# EVB-NORA-B2_SCHEM_0005_On-Board-Debug.net
KiCad netlist of a schematic drawn in Altium Designer
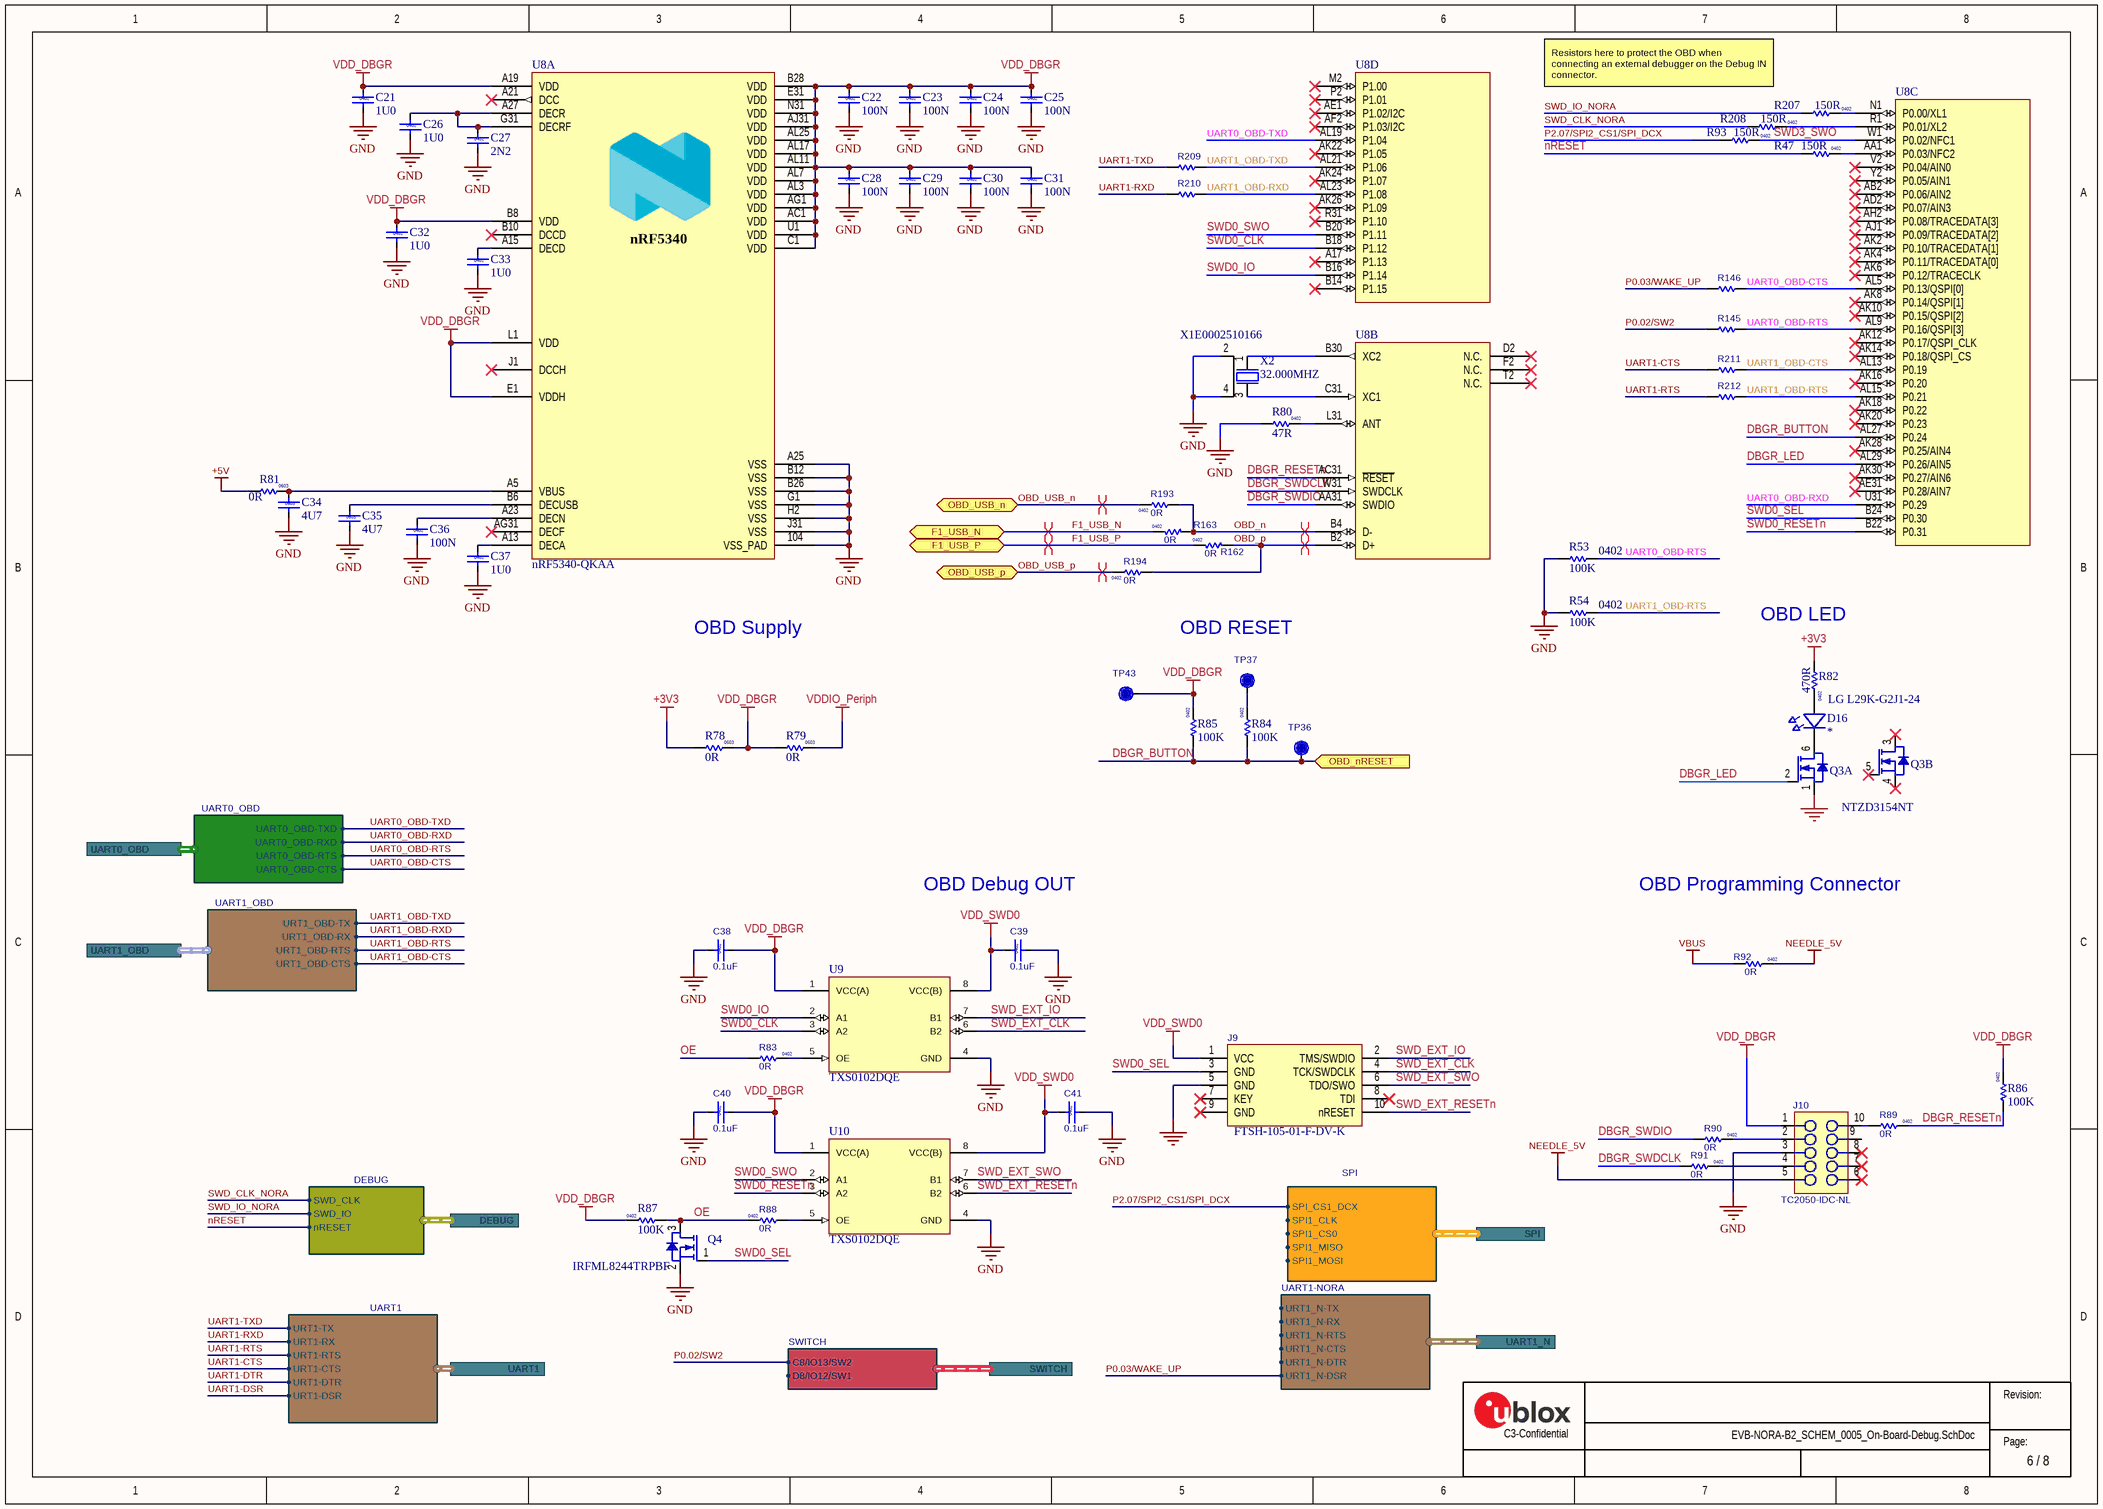
[diagram p0: EVB-NORA-B2_SCHEM_0005_On-Board-Debug.SchDoc]

(export (version "E")
  (design (tool "Eeschema 10.0.6"))
  (components
    (comp (ref "C21")
      (value "1U0")
      (footprint "Cap_0402_1100Lx600Wx600H_600x600Pad_350G_FLX")
      (description "CAP CER X5R 0402 1U0 10% 6.3V")
      (fields
        (field (name "SIZE") "0402")
        (field (name "PART NUMBER") "UBXH01-2021003")
        (field (name "TOLERANCE") "10%")
      )
      (libsource (lib "UBX_Parts_DB_Lib") (part "Cap Chip"))
    )
    (comp (ref "C22")
      (value "100N")
      (footprint "Cap 0402 HD")
      (description "CAP CER X5R 0402 100N 10% 10V")
      (fields
        (field (name "SIZE") "0402")
        (field (name "PART NUMBER") "UBXH01-2021002")
        (field (name "TOLERANCE") "10%")
      )
      (libsource (lib "UBX_Parts_DB_Lib") (part "Cap Chip"))
    )
    (comp (ref "C23")
      (value "100N")
      (footprint "Cap 0402 HD")
      (description "CAP CER X5R 0402 100N 10% 10V")
      (fields
        (field (name "SIZE") "0402")
        (field (name "PART NUMBER") "UBXH01-2021002")
        (field (name "TOLERANCE") "10%")
      )
      (libsource (lib "UBX_Parts_DB_Lib") (part "Cap Chip"))
    )
    (comp (ref "C24")
      (value "100N")
      (footprint "Cap 0402 HD")
      (description "CAP CER X5R 0402 100N 10% 10V")
      (fields
        (field (name "SIZE") "0402")
        (field (name "PART NUMBER") "UBXH01-2021002")
        (field (name "TOLERANCE") "10%")
      )
      (libsource (lib "UBX_Parts_DB_Lib") (part "Cap Chip"))
    )
    (comp (ref "C25")
      (value "100N")
      (footprint "Cap 0402 HD")
      (description "CAP CER X5R 0402 100N 10% 10V")
      (fields
        (field (name "SIZE") "0402")
        (field (name "PART NUMBER") "UBXH01-2021002")
        (field (name "TOLERANCE") "10%")
      )
      (libsource (lib "UBX_Parts_DB_Lib") (part "Cap Chip"))
    )
    (comp (ref "C26")
      (value "1U0")
      (footprint "Cap_0402_1100Lx600Wx600H_600x600Pad_350G_FLX")
      (description "CAP CER X5R 0402 1U0 10% 6.3V")
      (fields
        (field (name "SIZE") "0402")
        (field (name "PART NUMBER") "UBXH01-2021003")
        (field (name "TOLERANCE") "10%")
      )
      (libsource (lib "UBX_Parts_DB_Lib") (part "Cap Chip"))
    )
    (comp (ref "C27")
      (value "2N2")
      (footprint "Cap_0402_1100Lx600Wx600H_600x600Pad_350G_FLX")
      (description "CAP CER X7R 0402 2N2 10% 16V")
      (fields
        (field (name "SIZE") "0402")
        (field (name "PART NUMBER") "UBXH01-0023017")
        (field (name "TOLERANCE") "10%")
      )
      (libsource (lib "UBX_Parts_DB_Lib") (part "Cap Chip"))
    )
    (comp (ref "C28")
      (value "100N")
      (footprint "Cap 0402 HD")
      (description "CAP CER X5R 0402 100N 10% 10V")
      (fields
        (field (name "SIZE") "0402")
        (field (name "PART NUMBER") "UBXH01-2021002")
        (field (name "TOLERANCE") "10%")
      )
      (libsource (lib "UBX_Parts_DB_Lib") (part "Cap Chip"))
    )
    (comp (ref "C29")
      (value "100N")
      (footprint "Cap 0402 HD")
      (description "CAP CER X5R 0402 100N 10% 10V")
      (fields
        (field (name "SIZE") "0402")
        (field (name "PART NUMBER") "UBXH01-2021002")
        (field (name "TOLERANCE") "10%")
      )
      (libsource (lib "UBX_Parts_DB_Lib") (part "Cap Chip"))
    )
    (comp (ref "C30")
      (value "100N")
      (footprint "Cap 0402 HD")
      (description "CAP CER X5R 0402 100N 10% 10V")
      (fields
        (field (name "SIZE") "0402")
        (field (name "PART NUMBER") "UBXH01-2021002")
        (field (name "TOLERANCE") "10%")
      )
      (libsource (lib "UBX_Parts_DB_Lib") (part "Cap Chip"))
    )
    (comp (ref "C31")
      (value "100N")
      (footprint "Cap 0402 HD")
      (description "CAP CER X5R 0402 100N 10% 10V")
      (fields
        (field (name "SIZE") "0402")
        (field (name "PART NUMBER") "UBXH01-2021002")
        (field (name "TOLERANCE") "10%")
      )
      (libsource (lib "UBX_Parts_DB_Lib") (part "Cap Chip"))
    )
    (comp (ref "C32")
      (value "1U0")
      (footprint "Cap_0402_1100Lx600Wx600H_600x600Pad_350G_FLX")
      (description "CAP CER X5R 0402 1U0 10% 6.3V")
      (fields
        (field (name "SIZE") "0402")
        (field (name "PART NUMBER") "UBXH01-2021003")
        (field (name "TOLERANCE") "10%")
      )
      (libsource (lib "UBX_Parts_DB_Lib") (part "Cap Chip"))
    )
    (comp (ref "C33")
      (value "1U0")
      (footprint "Cap_0402_1100Lx600Wx600H_600x600Pad_350G_FLX")
      (description "CAP CER X5R 0402 1U0 10% 6.3V")
      (fields
        (field (name "SIZE") "0402")
        (field (name "PART NUMBER") "UBXH01-2021003")
        (field (name "TOLERANCE") "10%")
      )
      (libsource (lib "UBX_Parts_DB_Lib") (part "Cap Chip"))
    )
    (comp (ref "C34")
      (value "4U7")
      (footprint "CAP_0603_1750Lx950Wx850H_600x1000Pad_900G_FLX")
      (description "CAP CER X5R 0603 4U7 10% 6.3V")
      (fields
        (field (name "SIZE") "0603")
        (field (name "PART NUMBER") "UBXH01-2002003")
        (field (name "TOLERANCE") "10%")
      )
      (libsource (lib "UBX_Parts_DB_Lib") (part "Cap Chip"))
    )
    (comp (ref "C35")
      (value "4U7")
      (footprint "CAP_0603_1750Lx950Wx850H_600x1000Pad_900G_FLX")
      (description "CAP CER X5R 0603 4U7 10% 6.3V")
      (fields
        (field (name "SIZE") "0603")
        (field (name "PART NUMBER") "UBXH01-2002003")
        (field (name "TOLERANCE") "10%")
      )
      (libsource (lib "UBX_Parts_DB_Lib") (part "Cap Chip"))
    )
    (comp (ref "C36")
      (value "100N")
      (footprint "Cap 0402 HD")
      (description "CAP CER X5R 0402 100N 10% 10V")
      (fields
        (field (name "SIZE") "0402")
        (field (name "PART NUMBER") "UBXH01-2021002")
        (field (name "TOLERANCE") "10%")
      )
      (libsource (lib "UBX_Parts_DB_Lib") (part "Cap Chip"))
    )
    (comp (ref "C37")
      (value "1U0")
      (footprint "Cap_0402_1100Lx600Wx600H_600x600Pad_350G_FLX")
      (description "CAP CER X5R 0402 1U0 10% 6.3V")
      (fields
        (field (name "SIZE") "0402")
        (field (name "PART NUMBER") "UBXH01-2021003")
        (field (name "TOLERANCE") "10%")
      )
      (libsource (lib "UBX_Parts_DB_Lib") (part "Cap Chip"))
    )
    (comp (ref "C38")
      (value "0.1uF")
      (footprint "Cap 0402 HD")
      (description "Cap, Ceramic 0.1uF 10V 10% X5R 0402")
      (fields
        (field (name "SIZE") "0402")
        (field (name "PART NUMBER") "120-00016")
        (field (name "MANUFACTURER") "Murata Electronics North America")
      )
      (libsource (lib "Arena_Parts_DB_Lib") (part "Cap Chip"))
    )
    (comp (ref "C39")
      (value "0.1uF")
      (footprint "Cap 0402 HD")
      (description "Cap, Ceramic 0.1uF 10V 10% X5R 0402")
      (fields
        (field (name "SIZE") "0402")
        (field (name "PART NUMBER") "120-00016")
        (field (name "MANUFACTURER") "Murata Electronics North America")
      )
      (libsource (lib "Arena_Parts_DB_Lib") (part "Cap Chip"))
    )
    (comp (ref "C40")
      (value "0.1uF")
      (footprint "Cap 0402 HD")
      (description "Cap, Ceramic 0.1uF 10V 10% X5R 0402")
      (fields
        (field (name "SIZE") "0402")
        (field (name "PART NUMBER") "120-00016")
        (field (name "MANUFACTURER") "Murata Electronics North America")
      )
      (libsource (lib "Arena_Parts_DB_Lib") (part "Cap Chip"))
    )
    (comp (ref "C41")
      (value "0.1uF")
      (footprint "Cap 0402 HD")
      (description "Cap, Ceramic 0.1uF 10V 10% X5R 0402")
      (fields
        (field (name "SIZE") "0402")
        (field (name "PART NUMBER") "120-00016")
        (field (name "MANUFACTURER") "Murata Electronics North America")
      )
      (libsource (lib "Arena_Parts_DB_Lib") (part "Cap Chip"))
    )
    (comp (ref "D16")
      (value "UBXH11-0000018")
      (footprint "LED_0603_1600Lx800Wx400H_600x800Pad_800G_FLX")
      (description "LED CHIP 0603 LOW CURRENT OSRAM 0.002A GREEN 2.2V 2mA")
      (fields
        (field (name "COLOR") "*")
        (field (name "MANUFACTURER") "Osram")
        (field (name "MANUFACTURER P/N") "LG L29K-G2J1-24")
      )
      (libsource (lib "UBX_Parts_DB_Lib") (part "LED_BASE"))
    )
    (comp (ref "J9")
      (value "130-00099")
      (footprint "HDR.050P-10Pin-2x5-SMT_Key")
      (description "Header 0.05\" 10Pin 2Row SMD Black")
      (fields (field (name "MANUFACTURER") "Samtec") (field (name "MANUFACTURER P/N") "FTSH-105-01-F-DV-K"))
      (libsource (lib "Arena_Parts_DB_Lib") (part "JTAG-10Pin"))
    )
    (comp (ref "J10")
      (value "TC2050-IDC-NL")
      (footprint "TC2050-IDC-NL")
      (description "CON PADS FOR CBL PLUG-OF-NAILS 10-PIN NO LEGS")
      (fields (field (name "MANUFACTURER P/N") "TC2050-IDC-NL") (field (name "MANUFACTURER") "TAG Connect"))
      (libsource (lib "LEGACY_Rigado_AltiumLib") (part "CON-10Pin_2Row_ALT"))
    )
    (comp (ref "Q3")
      (value "NTZD3154NT")
      (footprint "SOT-563")
      (description "DUAL N-CHANNEL SMALL SIGNAL MOSFET SOT-563-6 PACKAGE")
      (fields (field (name "MANUFACTURER") "ON Semiconductor") (field (name "PART NUMBER") "UBXH20-0000083"))
      (libsource (lib "UBX_Parts_DB_Lib") (part "MOSFET-N-Dual"))
    )
    (comp (ref "Q4")
      (value "IRFML8244TRPBF")
      (footprint "SOT-23")
      (description "N-CHANNEL 25V HEXFET SOT23 25V 5.8A")
      (fields
        (field (name "PART NUMBER") "UBXH20-0000036")
        (field (name "MANUFACTURER") "IR International Rectifier")
      )
      (libsource (lib "UBX_Parts_DB_Lib") (part "MOSFET-N"))
    )
    (comp (ref "R47")
      (value "150R")
      (footprint "RES_0402_1100Lx600Wx400H_500x600Pad_400G_FLX")
      (description "RES THICK FILM CHIP 0402 150R 5% 63mW")
      (fields
        (field (name "SIZE") "0402")
        (field (name "PART NUMBER") "UBXH18-0008029")
        (field (name "TOLERANCE") "5%")
      )
      (libsource (lib "UBX_Parts_DB_Lib") (part "Res sm"))
    )
    (comp (ref "R53")
      (value "100K")
      (footprint "RES 0402 HD")
      (description "RES THICK FILM CHIP 0402 100K 1% 63mW")
      (fields
        (field (name "SIZE") "0402")
        (field (name "PART NUMBER") "UBXH18-0000005")
        (field (name "TOLERANCE") "1%")
      )
      (libsource (lib "UBX_Parts_DB_Lib") (part "Res sm"))
    )
    (comp (ref "R54")
      (value "100K")
      (footprint "RES 0402 HD")
      (description "RES THICK FILM CHIP 0402 100K 1% 63mW")
      (fields
        (field (name "SIZE") "0402")
        (field (name "PART NUMBER") "UBXH18-0000005")
        (field (name "TOLERANCE") "1%")
      )
      (libsource (lib "UBX_Parts_DB_Lib") (part "Res sm"))
    )
    (comp (ref "R78")
      (value "0R")
      (footprint "RES_0603_1700Lx950Wx600H_600x1000Pad_800G_FLX")
      (description "RES THICK FILM CHIP 0603 0R 0 100mW")
      (fields
        (field (name "SIZE") "0603")
        (field (name "PART NUMBER") "UBXH18-0003001")
        (field (name "TOLERANCE") "0")
      )
      (libsource (lib "UBX_Parts_DB_Lib") (part "Res sm"))
    )
    (comp (ref "R79")
      (value "0R")
      (footprint "RES_0603_1700Lx950Wx600H_600x1000Pad_800G_FLX")
      (description "RES THICK FILM CHIP 0603 0R 0 100mW")
      (fields
        (field (name "SIZE") "0603")
        (field (name "PART NUMBER") "UBXH18-0003001")
        (field (name "TOLERANCE") "0")
      )
      (libsource (lib "UBX_Parts_DB_Lib") (part "Res sm"))
    )
    (comp (ref "R80")
      (value "47R")
      (footprint "RES_0402_1100Lx600Wx400H_500x600Pad_400G_FLX")
      (description "RES THICK FILM CHIP 0402 47R 5% 100mW")
      (fields
        (field (name "SIZE") "0402")
        (field (name "PART NUMBER") "UBXH18-0008017")
        (field (name "TOLERANCE") "5%")
      )
      (libsource (lib "UBX_Parts_DB_Lib") (part "Res sm"))
    )
    (comp (ref "R81")
      (value "0R")
      (footprint "RES_0603_1700Lx950Wx600H_600x1000Pad_800G_FLX")
      (description "RES THICK FILM CHIP 0603 0R 0 100mW")
      (fields
        (field (name "SIZE") "0603")
        (field (name "PART NUMBER") "UBXH18-0003001")
        (field (name "TOLERANCE") "0")
      )
      (libsource (lib "UBX_Parts_DB_Lib") (part "Res sm"))
    )
    (comp (ref "R82")
      (value "470R")
      (footprint "RES_0402_1100Lx600Wx400H_500x600Pad_400G_FLX")
      (description "RES THICK FILM CHIP 0402 470R 5% 100mW")
      (fields
        (field (name "SIZE") "0402")
        (field (name "PART NUMBER") "UBXH18-0008041")
        (field (name "TOLERANCE") "5%")
      )
      (libsource (lib "UBX_Parts_DB_Lib") (part "Res sm"))
    )
    (comp (ref "R83")
      (value "0R")
      (footprint "RES 0402 HD")
      (description "RES THICK FILM CHIP 0402 0R 0 100mW")
      (fields
        (field (name "SIZE") "0402")
        (field (name "PART NUMBER") "UBXH18-0003002")
        (field (name "TOLERANCE") "0")
      )
      (libsource (lib "UBX_Parts_DB_Lib") (part "Res sm"))
    )
    (comp (ref "R84")
      (value "100K")
      (footprint "RES 0402 HD")
      (description "RES THICK FILM CHIP 0402 100K 1% 63mW")
      (fields
        (field (name "SIZE") "0402")
        (field (name "PART NUMBER") "UBXH18-0000005")
        (field (name "TOLERANCE") "1%")
      )
      (libsource (lib "UBX_Parts_DB_Lib") (part "Res sm"))
    )
    (comp (ref "R85")
      (value "100K")
      (footprint "RES 0402 HD")
      (description "RES THICK FILM CHIP 0402 100K 1% 63mW")
      (fields
        (field (name "SIZE") "0402")
        (field (name "PART NUMBER") "UBXH18-0000005")
        (field (name "TOLERANCE") "1%")
      )
      (libsource (lib "UBX_Parts_DB_Lib") (part "Res sm"))
    )
    (comp (ref "R86")
      (value "100K")
      (footprint "RES 0402 HD")
      (description "RES THICK FILM CHIP 0402 100K 1% 63mW")
      (fields
        (field (name "SIZE") "0402")
        (field (name "PART NUMBER") "UBXH18-0000005")
        (field (name "TOLERANCE") "1%")
      )
      (libsource (lib "UBX_Parts_DB_Lib") (part "Res sm"))
    )
    (comp (ref "R87")
      (value "100K")
      (footprint "RES 0402 HD")
      (description "RES THICK FILM CHIP 0402 100K 1% 63mW")
      (fields
        (field (name "SIZE") "0402")
        (field (name "PART NUMBER") "UBXH18-0000005")
        (field (name "TOLERANCE") "1%")
      )
      (libsource (lib "UBX_Parts_DB_Lib") (part "Res sm"))
    )
    (comp (ref "R88")
      (value "0R")
      (footprint "RES 0402 HD")
      (description "RES THICK FILM CHIP 0402 0R 0 100mW")
      (fields
        (field (name "SIZE") "0402")
        (field (name "PART NUMBER") "UBXH18-0003002")
        (field (name "TOLERANCE") "0")
      )
      (libsource (lib "UBX_Parts_DB_Lib") (part "Res sm"))
    )
    (comp (ref "R89")
      (value "0R")
      (footprint "RES 0402 HD")
      (description "RES THICK FILM CHIP 0402 0R 0 100mW")
      (fields
        (field (name "SIZE") "0402")
        (field (name "PART NUMBER") "UBXH18-0003002")
        (field (name "TOLERANCE") "0")
      )
      (libsource (lib "UBX_Parts_DB_Lib") (part "Res sm"))
    )
    (comp (ref "R90")
      (value "0R")
      (footprint "RES 0402 HD")
      (description "RES THICK FILM CHIP 0402 0R 0 100mW")
      (fields
        (field (name "SIZE") "0402")
        (field (name "PART NUMBER") "UBXH18-0003002")
        (field (name "TOLERANCE") "0")
      )
      (libsource (lib "UBX_Parts_DB_Lib") (part "Res sm"))
    )
    (comp (ref "R91")
      (value "0R")
      (footprint "RES 0402 HD")
      (description "RES THICK FILM CHIP 0402 0R 0 100mW")
      (fields
        (field (name "SIZE") "0402")
        (field (name "PART NUMBER") "UBXH18-0003002")
        (field (name "TOLERANCE") "0")
      )
      (libsource (lib "UBX_Parts_DB_Lib") (part "Res sm"))
    )
    (comp (ref "R92")
      (value "0R")
      (footprint "RES 0402 HD")
      (description "RES THICK FILM CHIP 0402 0R 0 100mW")
      (fields
        (field (name "SIZE") "0402")
        (field (name "PART NUMBER") "UBXH18-0003002")
        (field (name "TOLERANCE") "0")
      )
      (libsource (lib "UBX_Parts_DB_Lib") (part "Res sm"))
    )
    (comp (ref "R93")
      (value "150R")
      (footprint "RES_0402_1100Lx600Wx400H_500x600Pad_400G_FLX")
      (description "RES THICK FILM CHIP 0402 150R 5% 63mW")
      (fields
        (field (name "SIZE") "0402")
        (field (name "PART NUMBER") "UBXH18-0008029")
        (field (name "TOLERANCE") "5%")
      )
      (libsource (lib "UBX_Parts_DB_Lib") (part "Res sm"))
    )
    (comp (ref "R145")
      (value "UBXH18-0003002")
      (footprint "RES 0402 HD")
      (description "RES THICK FILM CHIP 0402 0R 0 100mW")
      (fields (field (name "TOLERANCE") "0") (field (name "MANUFACTURER") "KOA"))
      (libsource (lib "UBX_Parts_DB_Lib") (part "Res sm"))
    )
    (comp (ref "R146")
      (value "UBXH18-0003002")
      (footprint "RES 0402 HD")
      (description "RES THICK FILM CHIP 0402 0R 0 100mW")
      (fields (field (name "TOLERANCE") "0") (field (name "MANUFACTURER") "KOA"))
      (libsource (lib "UBX_Parts_DB_Lib") (part "Res sm"))
    )
    (comp (ref "R162")
      (value "0R")
      (footprint "RES 0402 HD")
      (description "RES THICK FILM CHIP 0402 0R 0 100mW")
      (fields
        (field (name "SIZE") "0402")
        (field (name "PART NUMBER") "UBXH18-0003002")
        (field (name "TOLERANCE") "0")
      )
      (libsource (lib "UBX_Parts_DB_Lib") (part "Res sm"))
    )
    (comp (ref "R163")
      (value "0R")
      (footprint "RES 0402 HD")
      (description "RES THICK FILM CHIP 0402 0R 0 100mW")
      (fields
        (field (name "SIZE") "0402")
        (field (name "PART NUMBER") "UBXH18-0003002")
        (field (name "TOLERANCE") "0")
      )
      (libsource (lib "UBX_Parts_DB_Lib") (part "Res sm"))
    )
    (comp (ref "R193")
      (value "0R")
      (footprint "RES 0402 HD")
      (description "RES THICK FILM CHIP 0402 0R 0 100mW")
      (fields
        (field (name "SIZE") "0402")
        (field (name "PART NUMBER") "UBXH18-0003002")
        (field (name "TOLERANCE") "0")
      )
      (libsource (lib "UBX_Parts_DB_Lib") (part "Res sm"))
    )
    (comp (ref "R194")
      (value "0R")
      (footprint "RES 0402 HD")
      (description "RES THICK FILM CHIP 0402 0R 0 100mW")
      (fields
        (field (name "SIZE") "0402")
        (field (name "PART NUMBER") "UBXH18-0003002")
        (field (name "TOLERANCE") "0")
      )
      (libsource (lib "UBX_Parts_DB_Lib") (part "Res sm"))
    )
    (comp (ref "R207")
      (value "150R")
      (footprint "RES_0402_1100Lx600Wx400H_500x600Pad_400G_FLX")
      (description "RES THICK FILM CHIP 0402 150R 5% 63mW")
      (fields
        (field (name "SIZE") "0402")
        (field (name "PART NUMBER") "UBXH18-0008029")
        (field (name "TOLERANCE") "5%")
      )
      (libsource (lib "UBX_Parts_DB_Lib") (part "Res sm"))
    )
    (comp (ref "R208")
      (value "150R")
      (footprint "RES_0402_1100Lx600Wx400H_500x600Pad_400G_FLX")
      (description "RES THICK FILM CHIP 0402 150R 5% 63mW")
      (fields
        (field (name "SIZE") "0402")
        (field (name "PART NUMBER") "UBXH18-0008029")
        (field (name "TOLERANCE") "5%")
      )
      (libsource (lib "UBX_Parts_DB_Lib") (part "Res sm"))
    )
    (comp (ref "R209")
      (value "UBXH18-0003002")
      (footprint "RES 0402 HD")
      (description "RES THICK FILM CHIP 0402 0R 0 100mW")
      (fields (field (name "TOLERANCE") "0") (field (name "MANUFACTURER") "KOA"))
      (libsource (lib "UBX_Parts_DB_Lib") (part "Res sm"))
    )
    (comp (ref "R210")
      (value "UBXH18-0003002")
      (footprint "RES 0402 HD")
      (description "RES THICK FILM CHIP 0402 0R 0 100mW")
      (fields (field (name "TOLERANCE") "0") (field (name "MANUFACTURER") "KOA"))
      (libsource (lib "UBX_Parts_DB_Lib") (part "Res sm"))
    )
    (comp (ref "R211")
      (value "UBXH18-0003002")
      (footprint "RES 0402 HD")
      (description "RES THICK FILM CHIP 0402 0R 0 100mW")
      (fields (field (name "TOLERANCE") "0") (field (name "MANUFACTURER") "KOA"))
      (libsource (lib "UBX_Parts_DB_Lib") (part "Res sm"))
    )
    (comp (ref "R212")
      (value "UBXH18-0003002")
      (footprint "RES 0402 HD")
      (description "RES THICK FILM CHIP 0402 0R 0 100mW")
      (fields (field (name "TOLERANCE") "0") (field (name "MANUFACTURER") "KOA"))
      (libsource (lib "UBX_Parts_DB_Lib") (part "Res sm"))
    )
    (comp (ref "TP36")
      (value "TP10R")
      (footprint "TP10R")
      (description "Testpoint, Round 1.0mm Dia")
      (libsource (lib "LEGACY_Rigado_AltiumLib") (part "TP_R"))
    )
    (comp (ref "TP37")
      (value "TP10R")
      (footprint "TP10R")
      (description "Testpoint, Round 1.0mm Dia")
      (libsource (lib "LEGACY_Rigado_AltiumLib") (part "TP_R"))
    )
    (comp (ref "TP43")
      (value "TP10R")
      (footprint "TP10R")
      (description "Testpoint, Round 1.0mm Dia")
      (libsource (lib "LEGACY_Rigado_AltiumLib") (part "TP_R"))
    )
    (comp (ref "U8")
      (value "UBXH12-0000420")
      (footprint "nRF5340_AQFN94")
      (description "BT5/802.15.4 SOC NORDIC NRF5340 2.4GHZ")
      (fields
        (field (name "MANUFACTURER") "Nordic Semiconductor")
        (field (name "MANUFACTURER P/N") "nRF5340-QKAA")
      )
      (libsource (lib "UBX_Parts_DB_Lib") (part "nRF5340_qkaa"))
    )
    (comp (ref "U9")
      (value "TXS0102DQE")
      (footprint "DQE0008A")
      (description "TXS0102 2-BIT BIDIRECTIONAL VOLTAGE-LEVEL TRANSLATOR X2SON-8 TXS0102DQE 5.5V")
      (fields (field (name "PART NUMBER") "UBXH10-0000108") (field (name "MANUFACTURER") "Texas Instruments"))
      (libsource (lib "UBX_Parts_DB_Lib") (part "TXS0102DQE"))
    )
    (comp (ref "U10")
      (value "TXS0102DQE")
      (footprint "DQE0008A")
      (description "TXS0102 2-BIT BIDIRECTIONAL VOLTAGE-LEVEL TRANSLATOR X2SON-8 TXS0102DQE 5.5V")
      (fields (field (name "PART NUMBER") "UBXH10-0000108") (field (name "MANUFACTURER") "Texas Instruments"))
      (libsource (lib "UBX_Parts_DB_Lib") (part "TXS0102DQE"))
    )
    (comp (ref "X2")
      (value "32.000MHZ")
      (footprint "XTAL_1612")
      (description "CRYSTAL 32MHZ CL=8PF 1.6X1.2 MM 32.000MHZ +/-10PPM@25C+/-20PPM@-40/+85+/-1PPMAGEING")
      (fields
        (field (name "PART NUMBER") "UBXH21-0000240")
        (field (name "TOLERANCE") "+/-10PPM@25C+/-20PPM@-40/+85+/-1PPMAGEING")
        (field (name "MANUFACTURER P/N") "X1E0002510166")
      )
      (libsource (lib "UBX_Parts_DB_Lib") (part "XTAL_4Pin"))
    )
  )
  (nets
    (net (code "8") (name "+3V3") (class "Default")
      (node (ref "R78") (pin "1") (pinfunction "1_1") (pintype "passive"))
      (node (ref "R82") (pin "1") (pinfunction "1_1") (pintype "passive"))
    )
    (net (code "9") (name "+5V") (class "Default")
      (node (ref "R81") (pin "1") (pinfunction "1_1") (pintype "passive"))
    )
    (net (code "10") (name "/DBGR_BUTTON") (class "Default")
      (node (ref "R84") (pin "1") (pinfunction "1_1") (pintype "passive"))
      (node (ref "R85") (pin "1") (pinfunction "1_1") (pintype "passive"))
      (node (ref "TP36") (pin "1") (pintype "passive"))
      (node (ref "U8") (pin "AL27") (pinfunction "P0.24_AL27") (pintype "bidirectional"))
    )
    (net (code "11") (name "/DBGR_LED") (class "Default")
      (node (ref "Q3") (pin "2") (pinfunction "G1_2") (pintype "passive"))
      (node (ref "U8") (pin "AL29") (pinfunction "P0.26/AIN5_AL29") (pintype "bidirectional"))
    )
    (net (code "12") (name "/DBGR_RESETn") (class "Default")
      (node (ref "R86") (pin "1") (pinfunction "1_1") (pintype "passive"))
      (node (ref "R89") (pin "1") (pinfunction "1_1") (pintype "passive"))
      (node (ref "U8") (pin "AC31") (pinfunction "~{RESET}_AC31") (pintype "input"))
    )
    (net (code "13") (name "/DBGR_SWDCLK") (class "Default")
      (node (ref "R91") (pin "2") (pinfunction "2_2") (pintype "passive"))
      (node (ref "U8") (pin "W31") (pinfunction "SWDCLK_W31") (pintype "input"))
    )
    (net (code "14") (name "/DBGR_SWDIO") (class "Default")
      (node (ref "R90") (pin "2") (pinfunction "2_2") (pintype "passive"))
      (node (ref "U8") (pin "AA31") (pinfunction "SWDIO_AA31") (pintype "bidirectional"))
    )
    (net (code "15") (name "/F1_USB_N") (class "Default")
      (node (ref "R163") (pin "2") (pinfunction "2_2") (pintype "passive"))
    )
    (net (code "16") (name "/F1_USB_P") (class "Default")
      (node (ref "R162") (pin "2") (pinfunction "2_2") (pintype "passive"))
    )
    (net (code "17") (name "/OBD_USB_n") (class "Default")
      (node (ref "R193") (pin "2") (pinfunction "2_2") (pintype "passive"))
    )
    (net (code "18") (name "/OBD_USB_p") (class "Default")
      (node (ref "R194") (pin "2") (pinfunction "2_2") (pintype "passive"))
    )
    (net (code "19") (name "/OBD_n") (class "Default")
      (node (ref "R163") (pin "1") (pinfunction "1_1") (pintype "passive"))
      (node (ref "R193") (pin "1") (pinfunction "1_1") (pintype "passive"))
      (node (ref "U8") (pin "B4") (pinfunction "D-_B4") (pintype "bidirectional"))
    )
    (net (code "20") (name "/OBD_p") (class "Default")
      (node (ref "R162") (pin "1") (pinfunction "1_1") (pintype "passive"))
      (node (ref "R194") (pin "1") (pinfunction "1_1") (pintype "passive"))
      (node (ref "U8") (pin "B2") (pinfunction "D+_B2") (pintype "bidirectional"))
    )
    (net (code "21") (name "/OE") (class "Default")
      (node (ref "Q4") (pin "3") (pinfunction "D_3") (pintype "passive"))
      (node (ref "R83") (pin "2") (pinfunction "2_2") (pintype "passive"))
      (node (ref "R87") (pin "1") (pinfunction "1_1") (pintype "passive"))
      (node (ref "R88") (pin "1") (pinfunction "1_1") (pintype "passive"))
    )
    (net (code "22") (name "/P0.02{slash}SW2") (class "Default")
      (node (ref "R145") (pin "2") (pinfunction "2_2") (pintype "passive"))
    )
    (net (code "23") (name "/P0.03{slash}WAKE_UP") (class "Default")
      (node (ref "R146") (pin "2") (pinfunction "2_2") (pintype "passive"))
    )
    (net (code "24") (name "/P2.07{slash}SPI2_CS1{slash}SPI_DCX") (class "Default")
      (node (ref "R93") (pin "1") (pinfunction "1_1") (pintype "passive"))
    )
    (net (code "25") (name "/SWD0_CLK") (class "Default")
      (node (ref "U8") (pin "B18") (pinfunction "P1.12_B18") (pintype "bidirectional"))
      (node (ref "U9") (pin "3") (pinfunction "A2_3") (pintype "bidirectional"))
    )
    (net (code "26") (name "/SWD0_IO") (class "Default")
      (node (ref "U8") (pin "B16") (pinfunction "P1.14_B16") (pintype "bidirectional"))
      (node (ref "U9") (pin "2") (pinfunction "A1_2") (pintype "bidirectional"))
    )
    (net (code "27") (name "/SWD0_RESETn") (class "Default")
      (node (ref "U10") (pin "3") (pinfunction "A2_3") (pintype "bidirectional"))
      (node (ref "U8") (pin "B22") (pinfunction "P0.31_B22") (pintype "bidirectional"))
    )
    (net (code "28") (name "/SWD0_SEL") (class "Default")
      (node (ref "J9") (pin "3") (pinfunction "GND_3") (pintype "passive"))
      (node (ref "Q4") (pin "1") (pinfunction "G_1") (pintype "passive"))
      (node (ref "U8") (pin "B24") (pinfunction "P0.30_B24") (pintype "bidirectional"))
    )
    (net (code "29") (name "/SWD0_SWO") (class "Default")
      (node (ref "U10") (pin "2") (pinfunction "A1_2") (pintype "bidirectional"))
      (node (ref "U8") (pin "B20") (pinfunction "P1.11_B20") (pintype "bidirectional"))
    )
    (net (code "30") (name "/SWD3_SWO") (class "Default")
      (node (ref "R93") (pin "2") (pinfunction "2_2") (pintype "passive"))
      (node (ref "U8") (pin "W1") (pinfunction "P0.02/NFC1_W1") (pintype "bidirectional"))
    )
    (net (code "31") (name "/SWD_CLK_NORA") (class "Default")
      (node (ref "R208") (pin "1") (pinfunction "1_1") (pintype "passive"))
    )
    (net (code "32") (name "/SWD_EXT_CLK") (class "Default")
      (node (ref "J9") (pin "4") (pinfunction "TCK/SWDCLK_4") (pintype "passive"))
      (node (ref "U9") (pin "6") (pinfunction "B2_6") (pintype "bidirectional"))
    )
    (net (code "33") (name "/SWD_EXT_IO") (class "Default")
      (node (ref "J9") (pin "2") (pinfunction "TMS/SWDIO_2") (pintype "passive"))
      (node (ref "U9") (pin "7") (pinfunction "B1_7") (pintype "bidirectional"))
    )
    (net (code "34") (name "/SWD_EXT_RESETn") (class "Default")
      (node (ref "J9") (pin "10") (pinfunction "nRESET_10") (pintype "passive"))
      (node (ref "U10") (pin "6") (pinfunction "B2_6") (pintype "bidirectional"))
    )
    (net (code "35") (name "/SWD_EXT_SWO") (class "Default")
      (node (ref "J9") (pin "6") (pinfunction "TDO/SWO_6") (pintype "passive"))
      (node (ref "U10") (pin "7") (pinfunction "B1_7") (pintype "bidirectional"))
    )
    (net (code "36") (name "/SWD_IO_NORA") (class "Default")
      (node (ref "R207") (pin "1") (pinfunction "1_1") (pintype "passive"))
    )
    (net (code "37") (name "/UART0_OBD-CTS") (class "Default")
      (node (ref "R146") (pin "1") (pinfunction "1_1") (pintype "passive"))
      (node (ref "U8") (pin "AL5") (pinfunction "P0.13/QSPI[0]_AL5") (pintype "bidirectional"))
    )
    (net (code "38") (name "/UART0_OBD-RTS") (class "Default")
      (node (ref "R145") (pin "1") (pinfunction "1_1") (pintype "passive"))
      (node (ref "R53") (pin "2") (pinfunction "2_2") (pintype "passive"))
      (node (ref "U8") (pin "AL9") (pinfunction "P0.16/QSPI[3]_AL9") (pintype "bidirectional"))
    )
    (net (code "39") (name "/UART0_OBD-RXD") (class "Default")
      (node (ref "U8") (pin "U31") (pinfunction "P0.29_U31") (pintype "bidirectional"))
    )
    (net (code "40") (name "/UART0_OBD-TXD") (class "Default")
      (node (ref "U8") (pin "AL19") (pinfunction "P1.04_AL19") (pintype "bidirectional"))
    )
    (net (code "41") (name "/UART1-CTS") (class "Default")
      (node (ref "R211") (pin "2") (pinfunction "2_2") (pintype "passive"))
    )
    (net (code "44") (name "/UART1-RTS") (class "Default")
      (node (ref "R212") (pin "2") (pinfunction "2_2") (pintype "passive"))
    )
    (net (code "45") (name "/UART1-RXD") (class "Default")
      (node (ref "R210") (pin "2") (pinfunction "2_2") (pintype "passive"))
    )
    (net (code "46") (name "/UART1-TXD") (class "Default")
      (node (ref "R209") (pin "2") (pinfunction "2_2") (pintype "passive"))
    )
    (net (code "47") (name "/UART1_OBD-CTS") (class "Default")
      (node (ref "R211") (pin "1") (pinfunction "1_1") (pintype "passive"))
      (node (ref "U8") (pin "AL13") (pinfunction "P0.19_AL13") (pintype "bidirectional"))
    )
    (net (code "48") (name "/UART1_OBD-RTS") (class "Default")
      (node (ref "R212") (pin "1") (pinfunction "1_1") (pintype "passive"))
      (node (ref "R54") (pin "2") (pinfunction "2_2") (pintype "passive"))
      (node (ref "U8") (pin "AL15") (pinfunction "P0.21_AL15") (pintype "bidirectional"))
    )
    (net (code "49") (name "/UART1_OBD-RXD") (class "Default")
      (node (ref "R210") (pin "1") (pinfunction "1_1") (pintype "passive"))
      (node (ref "U8") (pin "AL23") (pinfunction "P1.08_AL23") (pintype "bidirectional"))
    )
    (net (code "50") (name "/UART1_OBD-TXD") (class "Default")
      (node (ref "R209") (pin "1") (pinfunction "1_1") (pintype "passive"))
      (node (ref "U8") (pin "AL21") (pinfunction "P1.06_AL21") (pintype "bidirectional"))
    )
    (net (code "51") (name "/nRESET") (class "Default")
      (node (ref "R47") (pin "1") (pinfunction "1_1") (pintype "passive"))
    )
    (net (code "59") (name "GND") (class "Default")
      (node (ref "C21") (pin "2") (pinfunction "2_2") (pintype "passive"))
      (node (ref "C22") (pin "2") (pinfunction "2_2") (pintype "passive"))
      (node (ref "C23") (pin "2") (pinfunction "2_2") (pintype "passive"))
      (node (ref "C24") (pin "2") (pinfunction "2_2") (pintype "passive"))
      (node (ref "C25") (pin "2") (pinfunction "2_2") (pintype "passive"))
      (node (ref "C26") (pin "2") (pinfunction "2_2") (pintype "passive"))
      (node (ref "C27") (pin "2") (pinfunction "2_2") (pintype "passive"))
      (node (ref "C28") (pin "2") (pinfunction "2_2") (pintype "passive"))
      (node (ref "C29") (pin "2") (pinfunction "2_2") (pintype "passive"))
      (node (ref "C30") (pin "2") (pinfunction "2_2") (pintype "passive"))
      (node (ref "C31") (pin "2") (pinfunction "2_2") (pintype "passive"))
      (node (ref "C32") (pin "2") (pinfunction "2_2") (pintype "passive"))
      (node (ref "C33") (pin "2") (pinfunction "2_2") (pintype "passive"))
      (node (ref "C34") (pin "2") (pinfunction "2_2") (pintype "passive"))
      (node (ref "C35") (pin "2") (pinfunction "2_2") (pintype "passive"))
      (node (ref "C36") (pin "2") (pinfunction "2_2") (pintype "passive"))
      (node (ref "C37") (pin "2") (pinfunction "2_2") (pintype "passive"))
      (node (ref "C38") (pin "1") (pinfunction "1_1") (pintype "passive"))
      (node (ref "C39") (pin "2") (pinfunction "2_2") (pintype "passive"))
      (node (ref "C40") (pin "1") (pinfunction "1_1") (pintype "passive"))
      (node (ref "C41") (pin "2") (pinfunction "2_2") (pintype "passive"))
      (node (ref "J10") (pin "3") (pintype "passive"))
      (node (ref "J9") (pin "5") (pinfunction "GND_5") (pintype "passive"))
      (node (ref "Q3") (pin "1") (pinfunction "S1_1") (pintype "passive"))
      (node (ref "Q4") (pin "2") (pinfunction "S_2") (pintype "passive"))
      (node (ref "R53") (pin "1") (pinfunction "1_1") (pintype "passive"))
      (node (ref "R54") (pin "1") (pinfunction "1_1") (pintype "passive"))
      (node (ref "R80") (pin "1") (pinfunction "1_1") (pintype "passive"))
      (node (ref "U10") (pin "4") (pinfunction "GND_4") (pintype "power_in"))
      (node (ref "U8") (pin "104") (pinfunction "VSS_PAD_104") (pintype "power_in"))
      (node (ref "U8") (pin "A25") (pinfunction "VSS_A25") (pintype "power_in"))
      (node (ref "U8") (pin "B12") (pinfunction "VSS_B12") (pintype "power_in"))
      (node (ref "U8") (pin "B26") (pinfunction "VSS_B26") (pintype "power_in"))
      (node (ref "U8") (pin "G1") (pinfunction "VSS_G1") (pintype "power_in"))
      (node (ref "U8") (pin "H2") (pinfunction "VSS_H2") (pintype "power_in"))
      (node (ref "U8") (pin "J31") (pinfunction "VSS_J31") (pintype "power_in"))
      (node (ref "U9") (pin "4") (pinfunction "GND_4") (pintype "power_in"))
      (node (ref "X2") (pin "2") (pintype "passive"))
      (node (ref "X2") (pin "4") (pintype "passive"))
    )
    (net (code "60") (name "NEEDLE_5V") (class "Default")
      (node (ref "J10") (pin "5") (pintype "passive"))
      (node (ref "R92") (pin "1") (pinfunction "1_1") (pintype "passive"))
    )
    (net (code "61") (name "Net-(D16-A)") (class "Default")
      (node (ref "D16") (pin "2") (pinfunction "A_2") (pintype "passive"))
      (node (ref "R82") (pin "2") (pinfunction "2_2") (pintype "passive"))
    )
    (net (code "62") (name "Net-(D16-C)") (class "Default")
      (node (ref "D16") (pin "1") (pinfunction "C_1") (pintype "passive"))
      (node (ref "Q3") (pin "6") (pinfunction "D1_6") (pintype "passive"))
    )
    (net (code "63") (name "Net-(J10-Pad2)") (class "Default")
      (node (ref "J10") (pin "2") (pintype "passive"))
      (node (ref "R90") (pin "1") (pinfunction "1_1") (pintype "passive"))
    )
    (net (code "64") (name "Net-(J10-Pad4)") (class "Default")
      (node (ref "J10") (pin "4") (pintype "passive"))
      (node (ref "R91") (pin "1") (pinfunction "1_1") (pintype "passive"))
    )
    (net (code "65") (name "Net-(J10-Pad10)") (class "Default")
      (node (ref "J10") (pin "10") (pintype "passive"))
      (node (ref "R89") (pin "2") (pinfunction "2_2") (pintype "passive"))
    )
    (net (code "66") (name "Net-(R84-Pad2)") (class "Default")
      (node (ref "R84") (pin "2") (pinfunction "2_2") (pintype "passive"))
      (node (ref "TP37") (pin "1") (pintype "passive"))
    )
    (net (code "67") (name "Net-(U8A-DECA)") (class "Default")
      (node (ref "C37") (pin "1") (pinfunction "1_1") (pintype "passive"))
      (node (ref "U8") (pin "A13") (pinfunction "DECA_A13") (pintype "power_in"))
    )
    (net (code "68") (name "Net-(U8A-DECD)") (class "Default")
      (node (ref "C33") (pin "1") (pinfunction "1_1") (pintype "passive"))
      (node (ref "U8") (pin "A15") (pinfunction "DECD_A15") (pintype "power_in"))
    )
    (net (code "69") (name "Net-(U8A-DECN)") (class "Default")
      (node (ref "C36") (pin "1") (pinfunction "1_1") (pintype "passive"))
      (node (ref "U8") (pin "A23") (pinfunction "DECN_A23") (pintype "power_in"))
    )
    (net (code "70") (name "Net-(U8A-DECR)") (class "Default")
      (node (ref "C26") (pin "1") (pinfunction "1_1") (pintype "passive"))
      (node (ref "C27") (pin "1") (pinfunction "1_1") (pintype "passive"))
      (node (ref "U8") (pin "A27") (pinfunction "DECR_A27") (pintype "power_in"))
      (node (ref "U8") (pin "G31") (pinfunction "DECRF_G31") (pintype "power_in"))
    )
    (net (code "71") (name "Net-(U8A-DECUSB)") (class "Default")
      (node (ref "C35") (pin "1") (pinfunction "1_1") (pintype "passive"))
      (node (ref "U8") (pin "B6") (pinfunction "DECUSB_B6") (pintype "power_in"))
    )
    (net (code "72") (name "Net-(U8A-VBUS)") (class "Default")
      (node (ref "C34") (pin "1") (pinfunction "1_1") (pintype "passive"))
      (node (ref "R81") (pin "2") (pinfunction "2_2") (pintype "passive"))
      (node (ref "U8") (pin "A5") (pinfunction "VBUS_A5") (pintype "power_in"))
    )
    (net (code "73") (name "Net-(U8B-ANT)") (class "Default")
      (node (ref "R80") (pin "2") (pinfunction "2_2") (pintype "passive"))
      (node (ref "U8") (pin "L31") (pinfunction "ANT_L31") (pintype "bidirectional"))
    )
    (net (code "74") (name "Net-(U8B-XC1)") (class "Default")
      (node (ref "U8") (pin "C31") (pinfunction "XC1_C31") (pintype "input"))
      (node (ref "X2") (pin "3") (pintype "passive"))
    )
    (net (code "75") (name "Net-(U8B-XC2)") (class "Default")
      (node (ref "U8") (pin "B30") (pinfunction "XC2_B30") (pintype "output"))
      (node (ref "X2") (pin "1") (pintype "passive"))
    )
    (net (code "76") (name "Net-(U8C-P0.00{slash}XL1)") (class "Default")
      (node (ref "R207") (pin "2") (pinfunction "2_2") (pintype "passive"))
      (node (ref "U8") (pin "N1") (pinfunction "P0.00/XL1_N1") (pintype "bidirectional"))
    )
    (net (code "77") (name "Net-(U8C-P0.01{slash}XL2)") (class "Default")
      (node (ref "R208") (pin "2") (pinfunction "2_2") (pintype "passive"))
      (node (ref "U8") (pin "R1") (pinfunction "P0.01/XL2_R1") (pintype "bidirectional"))
    )
    (net (code "78") (name "Net-(U8C-P0.03{slash}NFC2)") (class "Default")
      (node (ref "R47") (pin "2") (pinfunction "2_2") (pintype "passive"))
      (node (ref "U8") (pin "AA1") (pinfunction "P0.03/NFC2_AA1") (pintype "bidirectional"))
    )
    (net (code "79") (name "Net-(U9-OE)") (class "Default")
      (node (ref "R83") (pin "1") (pinfunction "1_1") (pintype "passive"))
      (node (ref "U9") (pin "5") (pinfunction "OE_5") (pintype "input"))
    )
    (net (code "80") (name "Net-(U10-OE)") (class "Default")
      (node (ref "R88") (pin "2") (pinfunction "2_2") (pintype "passive"))
      (node (ref "U10") (pin "5") (pinfunction "OE_5") (pintype "input"))
    )
    (net (code "81") (name "VBUS") (class "Default")
      (node (ref "R92") (pin "2") (pinfunction "2_2") (pintype "passive"))
    )
    (net (code "82") (name "VDDIO_Periph") (class "Default")
      (node (ref "R79") (pin "2") (pinfunction "2_2") (pintype "passive"))
    )
    (net (code "83") (name "VDD_DBGR") (class "Default")
      (node (ref "C21") (pin "1") (pinfunction "1_1") (pintype "passive"))
      (node (ref "C22") (pin "1") (pinfunction "1_1") (pintype "passive"))
      (node (ref "C23") (pin "1") (pinfunction "1_1") (pintype "passive"))
      (node (ref "C24") (pin "1") (pinfunction "1_1") (pintype "passive"))
      (node (ref "C25") (pin "1") (pinfunction "1_1") (pintype "passive"))
      (node (ref "C28") (pin "1") (pinfunction "1_1") (pintype "passive"))
      (node (ref "C29") (pin "1") (pinfunction "1_1") (pintype "passive"))
      (node (ref "C30") (pin "1") (pinfunction "1_1") (pintype "passive"))
      (node (ref "C31") (pin "1") (pinfunction "1_1") (pintype "passive"))
      (node (ref "C32") (pin "1") (pinfunction "1_1") (pintype "passive"))
      (node (ref "C38") (pin "2") (pinfunction "2_2") (pintype "passive"))
      (node (ref "C40") (pin "2") (pinfunction "2_2") (pintype "passive"))
      (node (ref "J10") (pin "1") (pintype "passive"))
      (node (ref "R78") (pin "2") (pinfunction "2_2") (pintype "passive"))
      (node (ref "R79") (pin "1") (pinfunction "1_1") (pintype "passive"))
      (node (ref "R85") (pin "2") (pinfunction "2_2") (pintype "passive"))
      (node (ref "R86") (pin "2") (pinfunction "2_2") (pintype "passive"))
      (node (ref "R87") (pin "2") (pinfunction "2_2") (pintype "passive"))
      (node (ref "TP43") (pin "1") (pintype "passive"))
      (node (ref "U10") (pin "1") (pinfunction "VCC(A)_1") (pintype "power_in"))
      (node (ref "U8") (pin "A19") (pinfunction "VDD_A19") (pintype "power_in"))
      (node (ref "U8") (pin "AC1") (pinfunction "VDD_AC1") (pintype "power_in"))
      (node (ref "U8") (pin "AG1") (pinfunction "VDD_AG1") (pintype "power_in"))
      (node (ref "U8") (pin "AJ31") (pinfunction "VDD_AJ31") (pintype "power_in"))
      (node (ref "U8") (pin "AL11") (pinfunction "VDD_AL11") (pintype "power_in"))
      (node (ref "U8") (pin "AL17") (pinfunction "VDD_AL17") (pintype "power_in"))
      (node (ref "U8") (pin "AL25") (pinfunction "VDD_AL25") (pintype "power_in"))
      (node (ref "U8") (pin "AL3") (pinfunction "VDD_AL3") (pintype "power_in"))
      (node (ref "U8") (pin "AL7") (pinfunction "VDD_AL7") (pintype "power_in"))
      (node (ref "U8") (pin "B28") (pinfunction "VDD_B28") (pintype "power_in"))
      (node (ref "U8") (pin "B8") (pinfunction "VDD_B8") (pintype "power_in"))
      (node (ref "U8") (pin "C1") (pinfunction "VDD_C1") (pintype "power_in"))
      (node (ref "U8") (pin "E1") (pinfunction "VDDH_E1") (pintype "power_in"))
      (node (ref "U8") (pin "E31") (pinfunction "VDD_E31") (pintype "power_in"))
      (node (ref "U8") (pin "L1") (pinfunction "VDD_L1") (pintype "power_in"))
      (node (ref "U8") (pin "N31") (pinfunction "VDD_N31") (pintype "power_in"))
      (node (ref "U8") (pin "U1") (pinfunction "VDD_U1") (pintype "power_in"))
      (node (ref "U9") (pin "1") (pinfunction "VCC(A)_1") (pintype "power_in"))
    )
    (net (code "84") (name "VDD_SWD0") (class "Default")
      (node (ref "C39") (pin "1") (pinfunction "1_1") (pintype "passive"))
      (node (ref "C41") (pin "1") (pinfunction "1_1") (pintype "passive"))
      (node (ref "J9") (pin "1") (pinfunction "VCC_1") (pintype "passive"))
      (node (ref "U10") (pin "8") (pinfunction "VCC(B)_8") (pintype "power_in"))
      (node (ref "U9") (pin "8") (pinfunction "VCC(B)_8") (pintype "power_in"))
    )
    (net (code "85") (name "unconnected-(J9-GND-Pad9)") (class "Default")
      (node (ref "J9") (pin "9") (pinfunction "GND_9") (pintype "passive+no_connect"))
    )
    (net (code "86") (name "unconnected-(J9-KEY-Pad7)") (class "Default")
      (node (ref "J9") (pin "7") (pinfunction "KEY_7") (pintype "passive+no_connect"))
    )
    (net (code "87") (name "unconnected-(J9-TDI-Pad8)") (class "Default")
      (node (ref "J9") (pin "8") (pinfunction "TDI_8") (pintype "passive+no_connect"))
    )
    (net (code "88") (name "unconnected-(J10-Pad6)") (class "Default")
      (node (ref "J10") (pin "6") (pintype "passive+no_connect"))
    )
    (net (code "89") (name "unconnected-(J10-Pad7)") (class "Default")
      (node (ref "J10") (pin "7") (pintype "passive+no_connect"))
    )
    (net (code "90") (name "unconnected-(J10-Pad8)") (class "Default")
      (node (ref "J10") (pin "8") (pintype "passive+no_connect"))
    )
    (net (code "91") (name "unconnected-(J10-Pad9)") (class "Default")
      (node (ref "J10") (pin "9") (pintype "passive"))
    )
    (net (code "92") (name "unconnected-(Q3B-D2-Pad3)") (class "Default")
      (node (ref "Q3") (pin "3") (pinfunction "D2_3") (pintype "passive+no_connect"))
    )
    (net (code "93") (name "unconnected-(Q3B-G2-Pad5)") (class "Default")
      (node (ref "Q3") (pin "5") (pinfunction "G2_5") (pintype "passive+no_connect"))
    )
    (net (code "94") (name "unconnected-(Q3B-S2-Pad4)") (class "Default")
      (node (ref "Q3") (pin "4") (pinfunction "S2_4") (pintype "passive+no_connect"))
    )
    (net (code "95") (name "unconnected-(U8A-DCC-PadA21)") (class "Default")
      (node (ref "U8") (pin "A21") (pinfunction "DCC_A21") (pintype "output+no_connect"))
    )
    (net (code "96") (name "unconnected-(U8A-DCCD-PadB10)") (class "Default")
      (node (ref "U8") (pin "B10") (pinfunction "DCCD_B10") (pintype "power_in+no_connect"))
    )
    (net (code "97") (name "unconnected-(U8A-DCCH-PadJ1)") (class "Default")
      (node (ref "U8") (pin "J1") (pinfunction "DCCH_J1") (pintype "power_in+no_connect"))
    )
    (net (code "98") (name "unconnected-(U8A-DECF-PadAG31)") (class "Default")
      (node (ref "U8") (pin "AG31") (pinfunction "DECF_AG31") (pintype "power_in+no_connect"))
    )
    (net (code "99") (name "unconnected-(U8B-N.C.-PadD2)") (class "Default")
      (node (ref "U8") (pin "D2") (pinfunction "N.C._D2") (pintype "passive+no_connect"))
    )
    (net (code "100") (name "unconnected-(U8B-N.C.-PadF2)") (class "Default")
      (node (ref "U8") (pin "F2") (pinfunction "N.C._F2") (pintype "passive+no_connect"))
    )
    (net (code "101") (name "unconnected-(U8B-N.C.-PadT2)") (class "Default")
      (node (ref "U8") (pin "T2") (pinfunction "N.C._T2") (pintype "passive+no_connect"))
    )
    (net (code "102") (name "unconnected-(U8C-P0.04{slash}AIN0-PadV2)") (class "Default")
      (node (ref "U8") (pin "V2") (pinfunction "P0.04/AIN0_V2") (pintype "bidirectional+no_connect"))
    )
    (net (code "103") (name "unconnected-(U8C-P0.05{slash}AIN1-PadY2)") (class "Default")
      (node (ref "U8") (pin "Y2") (pinfunction "P0.05/AIN1_Y2") (pintype "bidirectional+no_connect"))
    )
    (net (code "104") (name "unconnected-(U8C-P0.06{slash}AIN2-PadAB2)") (class "Default")
      (node (ref "U8") (pin "AB2") (pinfunction "P0.06/AIN2_AB2") (pintype "bidirectional+no_connect"))
    )
    (net (code "105") (name "unconnected-(U8C-P0.07{slash}AIN3-PadAD2)") (class "Default")
      (node (ref "U8") (pin "AD2") (pinfunction "P0.07/AIN3_AD2") (pintype "bidirectional+no_connect"))
    )
    (net (code "106") (name "unconnected-(U8C-P0.08{slash}TRACEDATA[3]-PadAH2)") (class "Default")
      (node (ref "U8") (pin "AH2") (pinfunction "P0.08/TRACEDATA[3]_AH2") (pintype "bidirectional+no_connect"))
    )
    (net (code "107") (name "unconnected-(U8C-P0.09{slash}TRACEDATA[2]-PadAJ1)") (class "Default")
      (node (ref "U8") (pin "AJ1") (pinfunction "P0.09/TRACEDATA[2]_AJ1") (pintype "bidirectional+no_connect"))
    )
    (net (code "108") (name "unconnected-(U8C-P0.10{slash}TRACEDATA[1]-PadAK2)") (class "Default")
      (node (ref "U8") (pin "AK2") (pinfunction "P0.10/TRACEDATA[1]_AK2") (pintype "bidirectional+no_connect"))
    )
    (net (code "109") (name "unconnected-(U8C-P0.11{slash}TRACEDATA[0]-PadAK4)") (class "Default")
      (node (ref "U8") (pin "AK4") (pinfunction "P0.11/TRACEDATA[0]_AK4") (pintype "bidirectional+no_connect"))
    )
    (net (code "110") (name "unconnected-(U8C-P0.12{slash}TRACECLK-PadAK6)") (class "Default")
      (node (ref "U8") (pin "AK6") (pinfunction "P0.12/TRACECLK_AK6") (pintype "bidirectional+no_connect"))
    )
    (net (code "111") (name "unconnected-(U8C-P0.14{slash}QSPI[1]-PadAK8)") (class "Default")
      (node (ref "U8") (pin "AK8") (pinfunction "P0.14/QSPI[1]_AK8") (pintype "bidirectional+no_connect"))
    )
    (net (code "112") (name "unconnected-(U8C-P0.15{slash}QSPI[2]-PadAK10)") (class "Default")
      (node (ref "U8") (pin "AK10") (pinfunction "P0.15/QSPI[2]_AK10") (pintype "bidirectional+no_connect"))
    )
    (net (code "113") (name "unconnected-(U8C-P0.17{slash}QSPI_CLK-PadAK12)") (class "Default")
      (node (ref "U8") (pin "AK12") (pinfunction "P0.17/QSPI_CLK_AK12") (pintype "bidirectional+no_connect"))
    )
    (net (code "114") (name "unconnected-(U8C-P0.18{slash}QSPI_CS-PadAK14)") (class "Default")
      (node (ref "U8") (pin "AK14") (pinfunction "P0.18/QSPI_CS_AK14") (pintype "bidirectional+no_connect"))
    )
    (net (code "115") (name "unconnected-(U8C-P0.20-PadAK16)") (class "Default")
      (node (ref "U8") (pin "AK16") (pinfunction "P0.20_AK16") (pintype "bidirectional+no_connect"))
    )
    (net (code "116") (name "unconnected-(U8C-P0.22-PadAK18)") (class "Default")
      (node (ref "U8") (pin "AK18") (pinfunction "P0.22_AK18") (pintype "bidirectional+no_connect"))
    )
    (net (code "117") (name "unconnected-(U8C-P0.23-PadAK20)") (class "Default")
      (node (ref "U8") (pin "AK20") (pinfunction "P0.23_AK20") (pintype "bidirectional+no_connect"))
    )
    (net (code "118") (name "unconnected-(U8C-P0.25{slash}AIN4-PadAK28)") (class "Default")
      (node (ref "U8") (pin "AK28") (pinfunction "P0.25/AIN4_AK28") (pintype "bidirectional+no_connect"))
    )
    (net (code "119") (name "unconnected-(U8C-P0.27{slash}AIN6-PadAK30)") (class "Default")
      (node (ref "U8") (pin "AK30") (pinfunction "P0.27/AIN6_AK30") (pintype "bidirectional+no_connect"))
    )
    (net (code "120") (name "unconnected-(U8C-P0.28{slash}AIN7-PadAE31)") (class "Default")
      (node (ref "U8") (pin "AE31") (pinfunction "P0.28/AIN7_AE31") (pintype "bidirectional+no_connect"))
    )
    (net (code "121") (name "unconnected-(U8D-P1.00-PadM2)") (class "Default")
      (node (ref "U8") (pin "M2") (pinfunction "P1.00_M2") (pintype "bidirectional+no_connect"))
    )
    (net (code "122") (name "unconnected-(U8D-P1.01-PadP2)") (class "Default")
      (node (ref "U8") (pin "P2") (pinfunction "P1.01_P2") (pintype "bidirectional+no_connect"))
    )
    (net (code "123") (name "unconnected-(U8D-P1.02{slash}I2C-PadAE1)") (class "Default")
      (node (ref "U8") (pin "AE1") (pinfunction "P1.02/I2C_AE1") (pintype "bidirectional+no_connect"))
    )
    (net (code "124") (name "unconnected-(U8D-P1.03{slash}I2C-PadAF2)") (class "Default")
      (node (ref "U8") (pin "AF2") (pinfunction "P1.03/I2C_AF2") (pintype "bidirectional+no_connect"))
    )
    (net (code "125") (name "unconnected-(U8D-P1.05-PadAK22)") (class "Default")
      (node (ref "U8") (pin "AK22") (pinfunction "P1.05_AK22") (pintype "bidirectional+no_connect"))
    )
    (net (code "126") (name "unconnected-(U8D-P1.07-PadAK24)") (class "Default")
      (node (ref "U8") (pin "AK24") (pinfunction "P1.07_AK24") (pintype "bidirectional+no_connect"))
    )
    (net (code "127") (name "unconnected-(U8D-P1.09-PadAK26)") (class "Default")
      (node (ref "U8") (pin "AK26") (pinfunction "P1.09_AK26") (pintype "bidirectional+no_connect"))
    )
    (net (code "128") (name "unconnected-(U8D-P1.10-PadR31)") (class "Default")
      (node (ref "U8") (pin "R31") (pinfunction "P1.10_R31") (pintype "bidirectional+no_connect"))
    )
    (net (code "129") (name "unconnected-(U8D-P1.13-PadA17)") (class "Default")
      (node (ref "U8") (pin "A17") (pinfunction "P1.13_A17") (pintype "bidirectional+no_connect"))
    )
    (net (code "130") (name "unconnected-(U8D-P1.15-PadB14)") (class "Default")
      (node (ref "U8") (pin "B14") (pinfunction "P1.15_B14") (pintype "bidirectional+no_connect"))
    )
  )
)
